# LaserLider.net
KiCad netlist of a schematic drawn in Altium Designer
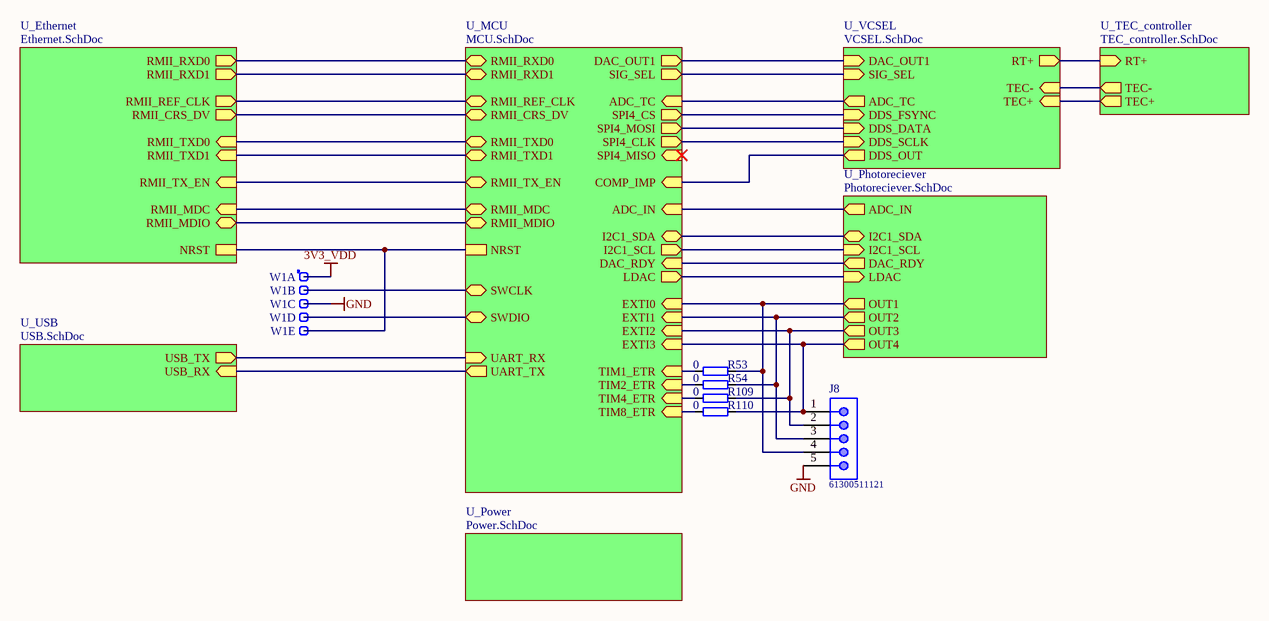
[diagram p0: LaserLider.SchDoc]

(export (version "E")
  (design (tool "Eeschema 10.0.6"))
  (components
    (comp (ref "J8")
      (value "61300511121")
      (footprint "61300511121")
      (description "WR-PHD Pin Header, THT, pitch 2.54mm, Single Row, Vertical, 5pin")
      (fields (field (name "PUBLISHER") "Wurth Elektronik"))
      (libsource (lib "ALTIUM-WR-PHD_PIN_HEADER_SOCKET_HEADER-rev19a") (part "61300511121"))
    )
    (comp (ref "R53")
      (value "0")
      (footprint "RESC1005X40N")
      (description "Resistor")
      (fields
        (field (name "PART NUMBER") "R0402_0R_JUMPER")
        (field (name "MANUFACTURER") "GENERIC")
        (field (name "AUTHOR") "CERN DEM JLC")
      )
      (libsource (lib "Resistors") (part "Resistor"))
    )
    (comp (ref "R54")
      (value "0")
      (footprint "RESC1005X40N")
      (description "Resistor")
      (fields
        (field (name "PART NUMBER") "R0402_0R_JUMPER")
        (field (name "MANUFACTURER") "GENERIC")
        (field (name "AUTHOR") "CERN DEM JLC")
      )
      (libsource (lib "Resistors") (part "Resistor"))
    )
    (comp (ref "R109")
      (value "0")
      (footprint "RESC1005X40N")
      (description "Resistor")
      (fields
        (field (name "PART NUMBER") "R0402_0R_JUMPER")
        (field (name "MANUFACTURER") "GENERIC")
        (field (name "AUTHOR") "CERN DEM JLC")
      )
      (libsource (lib "Resistors") (part "Resistor"))
    )
    (comp (ref "R110")
      (value "0")
      (footprint "RESC1005X40N")
      (description "Resistor")
      (fields
        (field (name "PART NUMBER") "R0402_0R_JUMPER")
        (field (name "MANUFACTURER") "GENERIC")
        (field (name "AUTHOR") "CERN DEM JLC")
      )
      (libsource (lib "Resistors") (part "Resistor"))
    )
    (comp (ref "W1")
      (value "Header 5")
      (footprint "SAMTEC_MTLW-105-07-L-S-250")
      (description "5 Mini Wire-Wrap Contact Strip Header")
      (fields
        (field (name "PART NUMBER") "SAMTEC_MTLW-105-07-L-S-250")
        (field (name "MANUFACTURER") "SAMTEC")
        (field (name "AUTHOR") "CERN DEM JLC")
      )
      (libsource (lib "Connectors") (part "Wire-Wrap Contact x5"))
    )
  )
  (nets
    (net (code "9") (name "/NRST") (class "Default")
      (node (ref "W1") (pin "5") (pinfunction "5_5") (pintype "bidirectional"))
    )
    (net (code "10") (name "/OUT1") (class "Default")
      (node (ref "J8") (pin "4") (pinfunction "4_4") (pintype "passive"))
      (node (ref "R53") (pin "2") (pinfunction "2_2") (pintype "passive"))
    )
    (net (code "11") (name "/OUT2") (class "Default")
      (node (ref "J8") (pin "3") (pinfunction "3_3") (pintype "passive"))
      (node (ref "R54") (pin "2") (pinfunction "2_2") (pintype "passive"))
    )
    (net (code "12") (name "/OUT3") (class "Default")
      (node (ref "J8") (pin "2") (pinfunction "2_2") (pintype "passive"))
      (node (ref "R109") (pin "2") (pinfunction "2_2") (pintype "passive"))
    )
    (net (code "13") (name "/OUT4") (class "Default")
      (node (ref "J8") (pin "1") (pinfunction "1_1") (pintype "passive"))
      (node (ref "R110") (pin "2") (pinfunction "2_2") (pintype "passive"))
    )
    (net (code "29") (name "/SWCLK") (class "Default")
      (node (ref "W1") (pin "2") (pinfunction "2_2") (pintype "bidirectional"))
    )
    (net (code "30") (name "/SWDIO") (class "Default")
      (node (ref "W1") (pin "4") (pinfunction "4_4") (pintype "bidirectional"))
    )
    (net (code "33") (name "/TIM1_ETR") (class "Default")
      (node (ref "R53") (pin "1") (pinfunction "1_1") (pintype "passive"))
    )
    (net (code "34") (name "/TIM2_ETR") (class "Default")
      (node (ref "R54") (pin "1") (pinfunction "1_1") (pintype "passive"))
    )
    (net (code "35") (name "/TIM4_ETR") (class "Default")
      (node (ref "R109") (pin "1") (pinfunction "1_1") (pintype "passive"))
    )
    (net (code "36") (name "/TIM8_ETR") (class "Default")
      (node (ref "R110") (pin "1") (pinfunction "1_1") (pintype "passive"))
    )
    (net (code "39") (name "3V3_VDD") (class "Default")
      (node (ref "W1") (pin "1") (pinfunction "1_1") (pintype "bidirectional"))
    )
    (net (code "40") (name "GND") (class "Default")
      (node (ref "J8") (pin "5") (pinfunction "5_5") (pintype "passive"))
      (node (ref "W1") (pin "3") (pinfunction "3_3") (pintype "bidirectional"))
    )
  )
)
